# Zio_Qwiic_Micropython_Pyboard_-STM32_V1_.net
KiCad netlist of a schematic drawn in EAGLE
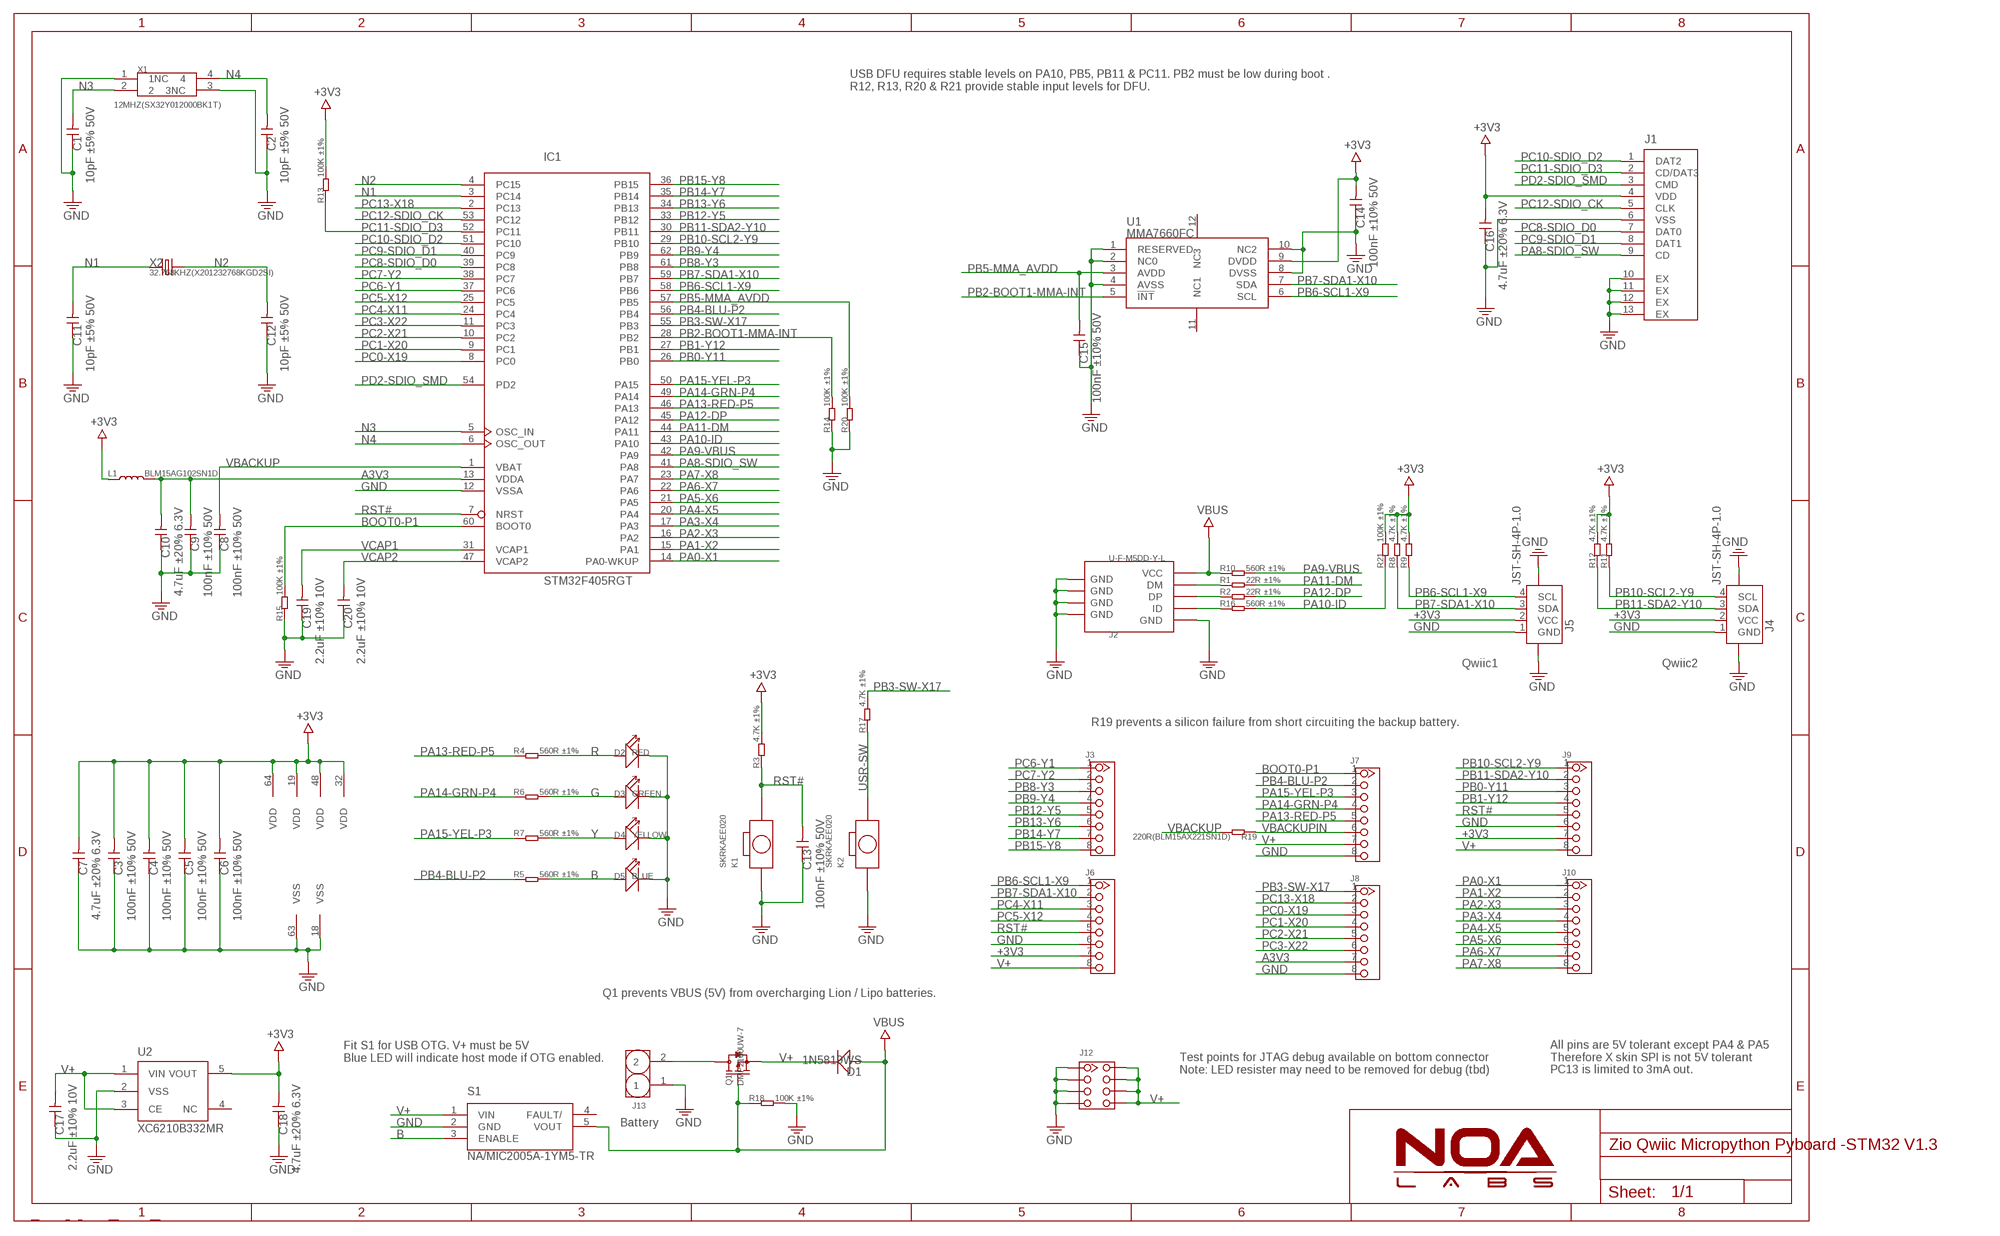
[diagram p0: schematic, sheet 1]

(export (version "E")
  (design (tool "Eeschema 10.0.6"))
  (components
    (comp (ref "C1")
      (value "10pF ±5% 50V")
      (footprint "eagle-import:C0402")
      (libsource (lib "eagle-import") (part "C-0402"))
    )
    (comp (ref "C2")
      (value "10pF ±5% 50V")
      (footprint "eagle-import:C0402")
      (libsource (lib "eagle-import") (part "C-0402"))
    )
    (comp (ref "C3")
      (value "100nF ±10% 50V")
      (footprint "eagle-import:C0402")
      (libsource (lib "eagle-import") (part "C-0402"))
    )
    (comp (ref "C4")
      (value "100nF ±10% 50V")
      (footprint "eagle-import:C0402")
      (libsource (lib "eagle-import") (part "C-0402"))
    )
    (comp (ref "C5")
      (value "100nF ±10% 50V")
      (footprint "eagle-import:C0402")
      (libsource (lib "eagle-import") (part "C-0402"))
    )
    (comp (ref "C6")
      (value "100nF ±10% 50V")
      (footprint "eagle-import:C0402")
      (libsource (lib "eagle-import") (part "C-0402"))
    )
    (comp (ref "C7")
      (value "4.7uF ±20% 6.3V")
      (footprint "eagle-import:C0402")
      (libsource (lib "eagle-import") (part "C-0402"))
    )
    (comp (ref "C8")
      (value "100nF ±10% 50V")
      (footprint "eagle-import:C0402")
      (libsource (lib "eagle-import") (part "C-0402"))
    )
    (comp (ref "C9")
      (value "100nF ±10% 50V")
      (footprint "eagle-import:C0402")
      (libsource (lib "eagle-import") (part "C-0402"))
    )
    (comp (ref "C10")
      (value "4.7uF ±20% 6.3V")
      (footprint "eagle-import:C0402")
      (libsource (lib "eagle-import") (part "C-0402"))
    )
    (comp (ref "C11")
      (value "10pF ±5% 50V")
      (footprint "eagle-import:C0402")
      (libsource (lib "eagle-import") (part "C-0402"))
    )
    (comp (ref "C12")
      (value "10pF ±5% 50V")
      (footprint "eagle-import:C0402")
      (libsource (lib "eagle-import") (part "C-0402"))
    )
    (comp (ref "C13")
      (value "100nF ±10% 50V")
      (footprint "eagle-import:C0402")
      (libsource (lib "eagle-import") (part "C-0402"))
    )
    (comp (ref "C14")
      (value "100nF ±10% 50V")
      (footprint "eagle-import:C0402")
      (libsource (lib "eagle-import") (part "C-0402"))
    )
    (comp (ref "C15")
      (value "100nF ±10% 50V")
      (footprint "eagle-import:C0402")
      (libsource (lib "eagle-import") (part "C-0402"))
    )
    (comp (ref "C16")
      (value "4.7uF ±20% 6.3V")
      (footprint "eagle-import:C0402")
      (libsource (lib "eagle-import") (part "C-0402"))
    )
    (comp (ref "C17")
      (value "2.2uF ±10% 10V")
      (footprint "eagle-import:C0402")
      (libsource (lib "eagle-import") (part "C-0402"))
    )
    (comp (ref "C18")
      (value "4.7uF ±20% 6.3V")
      (footprint "eagle-import:C0402")
      (libsource (lib "eagle-import") (part "C-0402"))
    )
    (comp (ref "C19")
      (value "2.2uF ±10% 10V")
      (footprint "eagle-import:C0402")
      (libsource (lib "eagle-import") (part "C-0402"))
    )
    (comp (ref "C20")
      (value "2.2uF ±10% 10V")
      (footprint "eagle-import:C0402")
      (libsource (lib "eagle-import") (part "C-0402"))
    )
    (comp (ref "D1")
      (value "1N5819WS")
      (footprint "eagle-import:SOD323")
      (libsource (lib "eagle-import") (part "D-0805"))
    )
    (comp (ref "D2")
      (value "RED")
      (footprint "eagle-import:LED-0603")
      (libsource (lib "eagle-import") (part "LED'0603'"))
    )
    (comp (ref "D3")
      (value "GREEN")
      (footprint "eagle-import:LED-0603")
      (libsource (lib "eagle-import") (part "LED'0603'"))
    )
    (comp (ref "D4")
      (value "YELLOW")
      (footprint "eagle-import:LED-0603")
      (libsource (lib "eagle-import") (part "LED'0603'"))
    )
    (comp (ref "D5")
      (value "BLUE")
      (footprint "eagle-import:LED-0603")
      (libsource (lib "eagle-import") (part "LED'0603'"))
    )
    (comp (ref "IC1")
      (value "STM32F405RGT")
      (footprint "eagle-import:LQFP64")
      (libsource (lib "eagle-import") (part "STM32F405RTG"))
    )
    (comp (ref "J1")
      (value "TF_CARD")
      (footprint "eagle-import:TF_CARD")
      (libsource (lib "eagle-import") (part "TF_CARD"))
    )
    (comp (ref "J2")
      (value "U-F-M5DD-Y-L")
      (footprint "eagle-import:MICRO-SMD")
      (libsource (lib "eagle-import") (part "USB-MICROE"))
    )
    (comp (ref "J3")
      (value "HEADER-8P-NS")
      (footprint "eagle-import:8P-2.54-60_35MIL-NS")
      (libsource (lib "eagle-import") (part "HEADER-8P-NS"))
    )
    (comp (ref "J4")
      (value "JST-SH-4P-1.0")
      (footprint "eagle-import:JST-SH-4P")
      (libsource (lib "eagle-import") (part "JST-SH-4P-1.0"))
    )
    (comp (ref "J5")
      (value "JST-SH-4P-1.0")
      (footprint "eagle-import:JST-SH-4P")
      (libsource (lib "eagle-import") (part "JST-SH-4P-1.0"))
    )
    (comp (ref "J6")
      (value "HEADER-8P-NS")
      (footprint "eagle-import:8P-2.54-60_35MIL-NS")
      (libsource (lib "eagle-import") (part "HEADER-8P-NS"))
    )
    (comp (ref "J7")
      (value "HEADER-8P-NS")
      (footprint "eagle-import:8P-2.54-60_35MIL-NS")
      (libsource (lib "eagle-import") (part "HEADER-8P-NS"))
    )
    (comp (ref "J8")
      (value "HEADER-8P-NS")
      (footprint "eagle-import:8P-2.54-60_35MIL-NS")
      (libsource (lib "eagle-import") (part "HEADER-8P-NS"))
    )
    (comp (ref "J9")
      (value "HEADER-8P-NS")
      (footprint "eagle-import:8P-2.54-60_35MIL-NS")
      (libsource (lib "eagle-import") (part "HEADER-8P-NS"))
    )
    (comp (ref "J10")
      (value "HEADER-8P-NS")
      (footprint "eagle-import:8P-2.54-60_35MIL-NS")
      (libsource (lib "eagle-import") (part "HEADER-8P-NS"))
    )
    (comp (ref "J12")
      (value "HEADER-2X4P-NS")
      (footprint "eagle-import:2X4P-2.54-NS")
      (libsource (lib "eagle-import") (part "HEADER-2X4P-NS"))
    )
    (comp (ref "J13")
      (value "HEADER-2P-2.0-90")
      (footprint "eagle-import:PH2.0-2P-90")
      (libsource (lib "eagle-import") (part "HEADER-2P-2.0-90"))
    )
    (comp (ref "K1")
      (value "SKRKAEE020")
      (footprint "eagle-import:SKRKAEE020")
      (libsource (lib "eagle-import") (part "BUTTON-2PSKRKAEE020"))
    )
    (comp (ref "K2")
      (value "SKRKAEE020")
      (footprint "eagle-import:SKRKAEE020")
      (libsource (lib "eagle-import") (part "BUTTON-2PSKRKAEE020"))
    )
    (comp (ref "L1")
      (value "BLM15AG102SN1D")
      (footprint "eagle-import:L0402")
      (libsource (lib "eagle-import") (part "L-0402"))
    )
    (comp (ref "Q1")
      (value "DMP2160UW-7")
      (footprint "eagle-import:SOT-323")
      (libsource (lib "eagle-import") (part "MOSFET-P-323"))
    )
    (comp (ref "R1")
      (value "22R ±1%")
      (footprint "eagle-import:R0402")
      (libsource (lib "eagle-import") (part "R-0402"))
    )
    (comp (ref "R2")
      (value "22R ±1%")
      (footprint "eagle-import:R0402")
      (libsource (lib "eagle-import") (part "R-0402"))
    )
    (comp (ref "R3")
      (value "4.7K ±1%")
      (footprint "eagle-import:R0402")
      (libsource (lib "eagle-import") (part "R-0402"))
    )
    (comp (ref "R4")
      (value "560R ±1%")
      (footprint "eagle-import:R0402")
      (libsource (lib "eagle-import") (part "R-0402"))
    )
    (comp (ref "R5")
      (value "560R ±1%")
      (footprint "eagle-import:R0402")
      (libsource (lib "eagle-import") (part "R-0402"))
    )
    (comp (ref "R6")
      (value "560R ±1%")
      (footprint "eagle-import:R0402")
      (libsource (lib "eagle-import") (part "R-0402"))
    )
    (comp (ref "R7")
      (value "560R ±1%")
      (footprint "eagle-import:R0402")
      (libsource (lib "eagle-import") (part "R-0402"))
    )
    (comp (ref "R8")
      (value "4.7K ±1%")
      (footprint "eagle-import:R0402")
      (libsource (lib "eagle-import") (part "R-0402"))
    )
    (comp (ref "R9")
      (value "4.7K ±1%")
      (footprint "eagle-import:R0402")
      (libsource (lib "eagle-import") (part "R-0402"))
    )
    (comp (ref "R10")
      (value "560R ±1%")
      (footprint "eagle-import:R0402")
      (libsource (lib "eagle-import") (part "R-0402"))
    )
    (comp (ref "R11")
      (value "4.7K ±1%")
      (footprint "eagle-import:R0402")
      (libsource (lib "eagle-import") (part "R-0402"))
    )
    (comp (ref "R12")
      (value "4.7K ±1%")
      (footprint "eagle-import:R0402")
      (libsource (lib "eagle-import") (part "R-0402"))
    )
    (comp (ref "R13")
      (value "100K ±1%")
      (footprint "eagle-import:R0402")
      (libsource (lib "eagle-import") (part "R-0402"))
    )
    (comp (ref "R14")
      (value "100K ±1%")
      (footprint "eagle-import:R0402")
      (libsource (lib "eagle-import") (part "R-0402"))
    )
    (comp (ref "R15")
      (value "100K ±1%")
      (footprint "eagle-import:R0402")
      (libsource (lib "eagle-import") (part "R-0402"))
    )
    (comp (ref "R16")
      (value "560R ±1%")
      (footprint "eagle-import:R0402")
      (libsource (lib "eagle-import") (part "R-0402"))
    )
    (comp (ref "R17")
      (value "4.7K ±1%")
      (footprint "eagle-import:R0402")
      (libsource (lib "eagle-import") (part "R-0402"))
    )
    (comp (ref "R18")
      (value "100K ±1%")
      (footprint "eagle-import:R0402")
      (libsource (lib "eagle-import") (part "R-0402"))
    )
    (comp (ref "R19")
      (value "220R(BLM15AX221SN1D)")
      (footprint "eagle-import:R0402")
      (libsource (lib "eagle-import") (part "R-0402"))
    )
    (comp (ref "R20")
      (value "100K ±1%")
      (footprint "eagle-import:R0402")
      (libsource (lib "eagle-import") (part "R-0402"))
    )
    (comp (ref "R21")
      (value "100K ±1%")
      (footprint "eagle-import:R0402")
      (libsource (lib "eagle-import") (part "R-0402"))
    )
    (comp (ref "S1")
      (value "NA/MIC2005A-1YM5-TR")
      (footprint "eagle-import:SOT95P280X130-5N")
      (fields
        (field (name "ARROW_PART_NUMBER") "MIC2005A-1YM5-TR")
        (field (name "MOUSER_PART_NUMBER") "998-MIC2005A-1YM5TR")
      )
      (libsource (lib "eagle-import") (part "MIC2005A-1YM5-TR"))
    )
    (comp (ref "U1")
      (value "MMA7660FC")
      (footprint "eagle-import:DFN10")
      (libsource (lib "eagle-import") (part "MMA7660FC-DFN10"))
    )
    (comp (ref "U2")
      (value "XC6210B332MR")
      (footprint "eagle-import:SOT23-5")
      (libsource (lib "eagle-import") (part "XC6210"))
    )
    (comp (ref "X1")
      (value "12MHZ(SX32Y012000BK1T)")
      (footprint "eagle-import:4P-SMD-3.2X2.5")
      (libsource (lib "eagle-import") (part "CRYSTAL-XTAL-4P-3225"))
    )
    (comp (ref "X2")
      (value "32.768KHZ(X201232768KGD2SI)")
      (footprint "eagle-import:2.0X12MM")
      (libsource (lib "eagle-import") (part "CRYSTAL-2012"))
    )
  )
  (nets
    (net (code "1") (name "+3V3") (class "Default")
      (node (ref "C14") (pin "2") (pinfunction "2_2") (pintype "passive"))
      (node (ref "C16") (pin "2") (pinfunction "2_2") (pintype "passive"))
      (node (ref "C18") (pin "2") (pinfunction "2_2") (pintype "passive"))
      (node (ref "C3") (pin "2") (pinfunction "2_2") (pintype "passive"))
      (node (ref "C4") (pin "2") (pinfunction "2_2") (pintype "passive"))
      (node (ref "C5") (pin "2") (pinfunction "2_2") (pintype "passive"))
      (node (ref "C6") (pin "2") (pinfunction "2_2") (pintype "passive"))
      (node (ref "C7") (pin "2") (pinfunction "2_2") (pintype "passive"))
      (node (ref "IC1") (pin "19") (pinfunction "VDD_19") (pintype "power_in"))
      (node (ref "IC1") (pin "32") (pinfunction "VDD_32") (pintype "power_in"))
      (node (ref "IC1") (pin "48") (pinfunction "VDD_48") (pintype "power_in"))
      (node (ref "IC1") (pin "64") (pinfunction "VDD_64") (pintype "power_in"))
      (node (ref "J1") (pin "4") (pinfunction "VDD_4") (pintype "bidirectional"))
      (node (ref "J4") (pin "2") (pinfunction "VCC_2") (pintype "bidirectional"))
      (node (ref "J5") (pin "2") (pinfunction "VCC_2") (pintype "bidirectional"))
      (node (ref "J6") (pin "7") (pinfunction "7_7") (pintype "bidirectional"))
      (node (ref "J9") (pin "7") (pinfunction "7_7") (pintype "bidirectional"))
      (node (ref "L1") (pin "1") (pinfunction "1_1") (pintype "passive"))
      (node (ref "R11") (pin "2") (pinfunction "2_2") (pintype "passive"))
      (node (ref "R12") (pin "2") (pinfunction "2_2") (pintype "passive"))
      (node (ref "R13") (pin "2") (pinfunction "2_2") (pintype "passive"))
      (node (ref "R21") (pin "2") (pinfunction "2_2") (pintype "passive"))
      (node (ref "R3") (pin "2") (pinfunction "2_2") (pintype "passive"))
      (node (ref "R8") (pin "2") (pinfunction "2_2") (pintype "passive"))
      (node (ref "R9") (pin "2") (pinfunction "2_2") (pintype "passive"))
      (node (ref "U1") (pin "9") (pinfunction "DVDD_9") (pintype "bidirectional"))
      (node (ref "U2") (pin "5") (pinfunction "VOUT_5") (pintype "bidirectional"))
    )
    (net (code "2") (name "/A3V3") (class "Default")
      (node (ref "C10") (pin "2") (pinfunction "2_2") (pintype "passive"))
      (node (ref "C9") (pin "2") (pinfunction "2_2") (pintype "passive"))
      (node (ref "IC1") (pin "13") (pinfunction "VDDA_13") (pintype "power_in"))
      (node (ref "J8") (pin "7") (pinfunction "7_7") (pintype "bidirectional"))
      (node (ref "L1") (pin "2") (pinfunction "2_2") (pintype "passive"))
    )
    (net (code "3") (name "/B") (class "Default")
      (node (ref "D5") (pin "+") (pinfunction "+_+") (pintype "passive"))
      (node (ref "R5") (pin "2") (pinfunction "2_2") (pintype "passive"))
      (node (ref "S1") (pin "3") (pinfunction "ENABLE_3") (pintype "bidirectional"))
    )
    (net (code "4") (name "/BOOT0-P1") (class "Default")
      (node (ref "IC1") (pin "60") (pinfunction "BOOT0_60") (pintype "input"))
      (node (ref "J7") (pin "1") (pinfunction "1_1") (pintype "bidirectional"))
      (node (ref "R15") (pin "2") (pinfunction "2_2") (pintype "passive"))
    )
    (net (code "5") (name "/G") (class "Default")
      (node (ref "D3") (pin "+") (pinfunction "+_+") (pintype "passive"))
      (node (ref "R6") (pin "2") (pinfunction "2_2") (pintype "passive"))
    )
    (net (code "6") (name "/N1") (class "Default")
      (node (ref "C11") (pin "2") (pinfunction "2_2") (pintype "passive"))
      (node (ref "IC1") (pin "3") (pinfunction "PC14_3") (pintype "bidirectional"))
      (node (ref "X2") (pin "1") (pinfunction "1_1") (pintype "passive"))
    )
    (net (code "7") (name "/N2") (class "Default")
      (node (ref "C12") (pin "2") (pinfunction "2_2") (pintype "passive"))
      (node (ref "IC1") (pin "4") (pinfunction "PC15_4") (pintype "bidirectional"))
      (node (ref "X2") (pin "2") (pinfunction "2_2") (pintype "passive"))
    )
    (net (code "8") (name "/N3") (class "Default")
      (node (ref "C1") (pin "2") (pinfunction "2_2") (pintype "passive"))
      (node (ref "IC1") (pin "5") (pinfunction "OSC_IN_5") (pintype "bidirectional"))
      (node (ref "X1") (pin "2") (pinfunction "2_2") (pintype "bidirectional"))
    )
    (net (code "9") (name "/N4") (class "Default")
      (node (ref "C2") (pin "2") (pinfunction "2_2") (pintype "passive"))
      (node (ref "IC1") (pin "6") (pinfunction "OSC_OUT_6") (pintype "bidirectional"))
      (node (ref "X1") (pin "4") (pinfunction "4_4") (pintype "bidirectional"))
    )
    (net (code "10") (name "/PA0-X1") (class "Default")
      (node (ref "IC1") (pin "14") (pinfunction "PA0-WKUP_14") (pintype "bidirectional"))
      (node (ref "J10") (pin "1") (pinfunction "1_1") (pintype "bidirectional"))
    )
    (net (code "11") (name "/PA1-X2") (class "Default")
      (node (ref "IC1") (pin "15") (pinfunction "PA1_15") (pintype "bidirectional"))
      (node (ref "J10") (pin "2") (pinfunction "2_2") (pintype "bidirectional"))
    )
    (net (code "12") (name "/PA2-X3") (class "Default")
      (node (ref "IC1") (pin "16") (pinfunction "PA2_16") (pintype "bidirectional"))
      (node (ref "J10") (pin "3") (pinfunction "3_3") (pintype "bidirectional"))
    )
    (net (code "13") (name "/PA3-X4") (class "Default")
      (node (ref "IC1") (pin "17") (pinfunction "PA3_17") (pintype "bidirectional"))
      (node (ref "J10") (pin "4") (pinfunction "4_4") (pintype "bidirectional"))
    )
    (net (code "14") (name "/PA4-X5") (class "Default")
      (node (ref "IC1") (pin "20") (pinfunction "PA4_20") (pintype "bidirectional"))
      (node (ref "J10") (pin "5") (pinfunction "5_5") (pintype "bidirectional"))
    )
    (net (code "15") (name "/PA5-X6") (class "Default")
      (node (ref "IC1") (pin "21") (pinfunction "PA5_21") (pintype "bidirectional"))
      (node (ref "J10") (pin "6") (pinfunction "6_6") (pintype "bidirectional"))
    )
    (net (code "16") (name "/PA6-X7") (class "Default")
      (node (ref "IC1") (pin "22") (pinfunction "PA6_22") (pintype "bidirectional"))
      (node (ref "J10") (pin "7") (pinfunction "7_7") (pintype "bidirectional"))
    )
    (net (code "17") (name "/PA7-X8") (class "Default")
      (node (ref "IC1") (pin "23") (pinfunction "PA7_23") (pintype "bidirectional"))
      (node (ref "J10") (pin "8") (pinfunction "8_8") (pintype "bidirectional"))
    )
    (net (code "18") (name "/PA8-SDIO_SW") (class "Default")
      (node (ref "IC1") (pin "41") (pinfunction "PA8_41") (pintype "bidirectional"))
      (node (ref "J1") (pin "9") (pinfunction "CD_9") (pintype "bidirectional"))
    )
    (net (code "19") (name "/PA9-VBUS") (class "Default")
      (node (ref "IC1") (pin "42") (pinfunction "PA9_42") (pintype "bidirectional"))
      (node (ref "R10") (pin "2") (pinfunction "2_2") (pintype "passive"))
    )
    (net (code "20") (name "/PA10-ID") (class "Default")
      (node (ref "IC1") (pin "43") (pinfunction "PA10_43") (pintype "bidirectional"))
      (node (ref "R16") (pin "2") (pinfunction "2_2") (pintype "passive"))
      (node (ref "R21") (pin "1") (pinfunction "1_1") (pintype "passive"))
    )
    (net (code "21") (name "/PA11-DM") (class "Default")
      (node (ref "IC1") (pin "44") (pinfunction "PA11_44") (pintype "bidirectional"))
      (node (ref "R1") (pin "2") (pinfunction "2_2") (pintype "passive"))
    )
    (net (code "22") (name "/PA12-DP") (class "Default")
      (node (ref "IC1") (pin "45") (pinfunction "PA12_45") (pintype "bidirectional"))
      (node (ref "R2") (pin "2") (pinfunction "2_2") (pintype "passive"))
    )
    (net (code "23") (name "/PA13-RED-P5") (class "Default")
      (node (ref "IC1") (pin "46") (pinfunction "PA13_46") (pintype "bidirectional"))
      (node (ref "J7") (pin "5") (pinfunction "5_5") (pintype "bidirectional"))
      (node (ref "R4") (pin "1") (pinfunction "1_1") (pintype "passive"))
    )
    (net (code "24") (name "/PA14-GRN-P4") (class "Default")
      (node (ref "IC1") (pin "49") (pinfunction "PA14_49") (pintype "bidirectional"))
      (node (ref "J7") (pin "4") (pinfunction "4_4") (pintype "bidirectional"))
      (node (ref "R6") (pin "1") (pinfunction "1_1") (pintype "passive"))
    )
    (net (code "25") (name "/PA15-YEL-P3") (class "Default")
      (node (ref "IC1") (pin "50") (pinfunction "PA15_50") (pintype "bidirectional"))
      (node (ref "J7") (pin "3") (pinfunction "3_3") (pintype "bidirectional"))
      (node (ref "R7") (pin "1") (pinfunction "1_1") (pintype "passive"))
    )
    (net (code "26") (name "/PB0-Y11") (class "Default")
      (node (ref "IC1") (pin "26") (pinfunction "PB0_26") (pintype "bidirectional"))
      (node (ref "J9") (pin "3") (pinfunction "3_3") (pintype "bidirectional"))
    )
    (net (code "27") (name "/PB1-Y12") (class "Default")
      (node (ref "IC1") (pin "27") (pinfunction "PB1_27") (pintype "bidirectional"))
      (node (ref "J9") (pin "4") (pinfunction "4_4") (pintype "bidirectional"))
    )
    (net (code "28") (name "/PB2-BOOT1-MMA-INT") (class "Default")
      (node (ref "IC1") (pin "28") (pinfunction "PB2_28") (pintype "bidirectional"))
      (node (ref "R14") (pin "2") (pinfunction "2_2") (pintype "passive"))
      (node (ref "U1") (pin "5") (pinfunction "~{INT}_5") (pintype "bidirectional"))
    )
    (net (code "29") (name "/PB3-SW-X17") (class "Default")
      (node (ref "IC1") (pin "55") (pinfunction "PB3_55") (pintype "bidirectional"))
      (node (ref "J8") (pin "1") (pinfunction "1_1") (pintype "bidirectional"))
      (node (ref "R17") (pin "2") (pinfunction "2_2") (pintype "passive"))
    )
    (net (code "30") (name "/PB4-BLU-P2") (class "Default")
      (node (ref "IC1") (pin "56") (pinfunction "PB4_56") (pintype "bidirectional"))
      (node (ref "J7") (pin "2") (pinfunction "2_2") (pintype "bidirectional"))
      (node (ref "R5") (pin "1") (pinfunction "1_1") (pintype "passive"))
    )
    (net (code "31") (name "/PB5-MMA_AVDD") (class "Default")
      (node (ref "C15") (pin "2") (pinfunction "2_2") (pintype "passive"))
      (node (ref "IC1") (pin "57") (pinfunction "PB5_57") (pintype "bidirectional"))
      (node (ref "R20") (pin "2") (pinfunction "2_2") (pintype "passive"))
      (node (ref "U1") (pin "3") (pinfunction "AVDD_3") (pintype "bidirectional"))
    )
    (net (code "32") (name "/PB6-SCL1-X9") (class "Default")
      (node (ref "IC1") (pin "58") (pinfunction "PB6_58") (pintype "bidirectional"))
      (node (ref "J5") (pin "4") (pinfunction "SCL_4") (pintype "bidirectional"))
      (node (ref "J6") (pin "1") (pinfunction "1_1") (pintype "bidirectional"))
      (node (ref "R9") (pin "1") (pinfunction "1_1") (pintype "passive"))
      (node (ref "U1") (pin "6") (pinfunction "SCL_6") (pintype "bidirectional"))
    )
    (net (code "33") (name "/PB7-SDA1-X10") (class "Default")
      (node (ref "IC1") (pin "59") (pinfunction "PB7_59") (pintype "bidirectional"))
      (node (ref "J5") (pin "3") (pinfunction "SDA_3") (pintype "bidirectional"))
      (node (ref "J6") (pin "2") (pinfunction "2_2") (pintype "bidirectional"))
      (node (ref "R8") (pin "1") (pinfunction "1_1") (pintype "passive"))
      (node (ref "U1") (pin "7") (pinfunction "SDA_7") (pintype "bidirectional"))
    )
    (net (code "34") (name "/PB8-Y3") (class "Default")
      (node (ref "IC1") (pin "61") (pinfunction "PB8_61") (pintype "bidirectional"))
      (node (ref "J3") (pin "3") (pinfunction "3_3") (pintype "bidirectional"))
    )
    (net (code "35") (name "/PB9-Y4") (class "Default")
      (node (ref "IC1") (pin "62") (pinfunction "PB9_62") (pintype "bidirectional"))
      (node (ref "J3") (pin "4") (pinfunction "4_4") (pintype "bidirectional"))
    )
    (net (code "36") (name "/PB10-SCL2-Y9") (class "Default")
      (node (ref "IC1") (pin "29") (pinfunction "PB10_29") (pintype "bidirectional"))
      (node (ref "J4") (pin "4") (pinfunction "SCL_4") (pintype "bidirectional"))
      (node (ref "J9") (pin "1") (pinfunction "1_1") (pintype "bidirectional"))
      (node (ref "R11") (pin "1") (pinfunction "1_1") (pintype "passive"))
    )
    (net (code "37") (name "/PB11-SDA2-Y10") (class "Default")
      (node (ref "IC1") (pin "30") (pinfunction "PB11_30") (pintype "bidirectional"))
      (node (ref "J4") (pin "3") (pinfunction "SDA_3") (pintype "bidirectional"))
      (node (ref "J9") (pin "2") (pinfunction "2_2") (pintype "bidirectional"))
      (node (ref "R12") (pin "1") (pinfunction "1_1") (pintype "passive"))
    )
    (net (code "38") (name "/PB12-Y5") (class "Default")
      (node (ref "IC1") (pin "33") (pinfunction "PB12_33") (pintype "bidirectional"))
      (node (ref "J3") (pin "5") (pinfunction "5_5") (pintype "bidirectional"))
    )
    (net (code "39") (name "/PB13-Y6") (class "Default")
      (node (ref "IC1") (pin "34") (pinfunction "PB13_34") (pintype "bidirectional"))
      (node (ref "J3") (pin "6") (pinfunction "6_6") (pintype "bidirectional"))
    )
    (net (code "40") (name "/PB14-Y7") (class "Default")
      (node (ref "IC1") (pin "35") (pinfunction "PB14_35") (pintype "bidirectional"))
      (node (ref "J3") (pin "7") (pinfunction "7_7") (pintype "bidirectional"))
    )
    (net (code "41") (name "/PB15-Y8") (class "Default")
      (node (ref "IC1") (pin "36") (pinfunction "PB15_36") (pintype "bidirectional"))
      (node (ref "J3") (pin "8") (pinfunction "8_8") (pintype "bidirectional"))
    )
    (net (code "42") (name "/PC0-X19") (class "Default")
      (node (ref "IC1") (pin "8") (pinfunction "PC0_8") (pintype "bidirectional"))
      (node (ref "J8") (pin "3") (pinfunction "3_3") (pintype "bidirectional"))
    )
    (net (code "43") (name "/PC1-X20") (class "Default")
      (node (ref "IC1") (pin "9") (pinfunction "PC1_9") (pintype "bidirectional"))
      (node (ref "J8") (pin "4") (pinfunction "4_4") (pintype "bidirectional"))
    )
    (net (code "44") (name "/PC2-X21") (class "Default")
      (node (ref "IC1") (pin "10") (pinfunction "PC2_10") (pintype "bidirectional"))
      (node (ref "J8") (pin "5") (pinfunction "5_5") (pintype "bidirectional"))
    )
    (net (code "45") (name "/PC3-X22") (class "Default")
      (node (ref "IC1") (pin "11") (pinfunction "PC3_11") (pintype "bidirectional"))
      (node (ref "J8") (pin "6") (pinfunction "6_6") (pintype "bidirectional"))
    )
    (net (code "46") (name "/PC4-X11") (class "Default")
      (node (ref "IC1") (pin "24") (pinfunction "PC4_24") (pintype "bidirectional"))
      (node (ref "J6") (pin "3") (pinfunction "3_3") (pintype "bidirectional"))
    )
    (net (code "47") (name "/PC5-X12") (class "Default")
      (node (ref "IC1") (pin "25") (pinfunction "PC5_25") (pintype "bidirectional"))
      (node (ref "J6") (pin "4") (pinfunction "4_4") (pintype "bidirectional"))
    )
    (net (code "48") (name "/PC6-Y1") (class "Default")
      (node (ref "IC1") (pin "37") (pinfunction "PC6_37") (pintype "bidirectional"))
      (node (ref "J3") (pin "1") (pinfunction "1_1") (pintype "bidirectional"))
    )
    (net (code "49") (name "/PC7-Y2") (class "Default")
      (node (ref "IC1") (pin "38") (pinfunction "PC7_38") (pintype "bidirectional"))
      (node (ref "J3") (pin "2") (pinfunction "2_2") (pintype "bidirectional"))
    )
    (net (code "50") (name "/PC8-SDIO_D0") (class "Default")
      (node (ref "IC1") (pin "39") (pinfunction "PC8_39") (pintype "bidirectional"))
      (node (ref "J1") (pin "7") (pinfunction "DAT0_7") (pintype "bidirectional"))
    )
    (net (code "51") (name "/PC9-SDIO_D1") (class "Default")
      (node (ref "IC1") (pin "40") (pinfunction "PC9_40") (pintype "bidirectional"))
      (node (ref "J1") (pin "8") (pinfunction "DAT1_8") (pintype "bidirectional"))
    )
    (net (code "52") (name "/PC10-SDIO_D2") (class "Default")
      (node (ref "IC1") (pin "51") (pinfunction "PC10_51") (pintype "bidirectional"))
      (node (ref "J1") (pin "1") (pinfunction "DAT2_1") (pintype "bidirectional"))
    )
    (net (code "53") (name "/PC11-SDIO_D3") (class "Default")
      (node (ref "IC1") (pin "52") (pinfunction "PC11_52") (pintype "bidirectional"))
      (node (ref "J1") (pin "2") (pinfunction "CD/DAT3_2") (pintype "bidirectional"))
      (node (ref "R13") (pin "1") (pinfunction "1_1") (pintype "passive"))
    )
    (net (code "54") (name "/PC12-SDIO_CK") (class "Default")
      (node (ref "IC1") (pin "53") (pinfunction "PC12_53") (pintype "bidirectional"))
      (node (ref "J1") (pin "5") (pinfunction "CLK_5") (pintype "bidirectional"))
    )
    (net (code "55") (name "/PC13-X18") (class "Default")
      (node (ref "IC1") (pin "2") (pinfunction "PC13_2") (pintype "bidirectional"))
      (node (ref "J8") (pin "2") (pinfunction "2_2") (pintype "bidirectional"))
    )
    (net (code "56") (name "/PD2-SDIO_SMD") (class "Default")
      (node (ref "IC1") (pin "54") (pinfunction "PD2_54") (pintype "bidirectional"))
      (node (ref "J1") (pin "3") (pinfunction "CMD_3") (pintype "bidirectional"))
    )
    (net (code "57") (name "/R") (class "Default")
      (node (ref "D2") (pin "+") (pinfunction "+_+") (pintype "passive"))
      (node (ref "R4") (pin "2") (pinfunction "2_2") (pintype "passive"))
    )
    (net (code "58") (name "/RST#") (class "Default")
      (node (ref "C13") (pin "2") (pinfunction "2_2") (pintype "passive"))
      (node (ref "IC1") (pin "7") (pinfunction "NRST_7") (pintype "bidirectional"))
      (node (ref "J6") (pin "5") (pinfunction "5_5") (pintype "bidirectional"))
      (node (ref "J9") (pin "5") (pinfunction "5_5") (pintype "bidirectional"))
      (node (ref "K1") (pin "2") (pinfunction "2_2") (pintype "bidirectional"))
      (node (ref "R3") (pin "1") (pinfunction "1_1") (pintype "passive"))
    )
    (net (code "59") (name "/USR-SW") (class "Default")
      (node (ref "K2") (pin "2") (pinfunction "2_2") (pintype "bidirectional"))
      (node (ref "R17") (pin "1") (pinfunction "1_1") (pintype "passive"))
    )
    (net (code "60") (name "/V+") (class "Default")
      (node (ref "C17") (pin "2") (pinfunction "2_2") (pintype "passive"))
      (node (ref "D1") (pin "-") (pinfunction "-_-") (pintype "passive"))
      (node (ref "J12") (pin "5") (pinfunction "5_5") (pintype "bidirectional"))
      (node (ref "J12") (pin "6") (pinfunction "6_6") (pintype "bidirectional"))
      (node (ref "J12") (pin "7") (pinfunction "7_7") (pintype "bidirectional"))
      (node (ref "J12") (pin "8") (pinfunction "8_8") (pintype "bidirectional"))
      (node (ref "J6") (pin "8") (pinfunction "8_8") (pintype "bidirectional"))
      (node (ref "J7") (pin "7") (pinfunction "7_7") (pintype "bidirectional"))
      (node (ref "J9") (pin "8") (pinfunction "8_8") (pintype "bidirectional"))
      (node (ref "Q1") (pin "2") (pinfunction "S_2") (pintype "passive"))
      (node (ref "S1") (pin "1") (pinfunction "VIN_1") (pintype "bidirectional"))
      (node (ref "U2") (pin "1") (pinfunction "VIN_1") (pintype "bidirectional"))
      (node (ref "U2") (pin "3") (pinfunction "CE_3") (pintype "bidirectional"))
    )
    (net (code "61") (name "/VBACKUP") (class "Default")
      (node (ref "C8") (pin "2") (pinfunction "2_2") (pintype "passive"))
      (node (ref "IC1") (pin "1") (pinfunction "VBAT_1") (pintype "power_in"))
      (node (ref "R19") (pin "2") (pinfunction "2_2") (pintype "passive"))
    )
    (net (code "62") (name "/VBACKUPIN") (class "Default")
      (node (ref "J7") (pin "6") (pinfunction "6_6") (pintype "bidirectional"))
      (node (ref "R19") (pin "1") (pinfunction "1_1") (pintype "passive"))
    )
    (net (code "63") (name "/VCAP1") (class "Default")
      (node (ref "C19") (pin "2") (pinfunction "2_2") (pintype "passive"))
      (node (ref "IC1") (pin "31") (pinfunction "VCAP1_31") (pintype "power_in"))
    )
    (net (code "64") (name "/VCAP2") (class "Default")
      (node (ref "C20") (pin "2") (pinfunction "2_2") (pintype "passive"))
      (node (ref "IC1") (pin "47") (pinfunction "VCAP2_47") (pintype "power_in"))
    )
    (net (code "65") (name "/Y") (class "Default")
      (node (ref "D4") (pin "+") (pinfunction "+_+") (pintype "passive"))
      (node (ref "R7") (pin "2") (pinfunction "2_2") (pintype "passive"))
    )
    (net (code "66") (name "GND") (class "Default")
      (node (ref "C1") (pin "1") (pinfunction "1_1") (pintype "passive"))
      (node (ref "C10") (pin "1") (pinfunction "1_1") (pintype "passive"))
      (node (ref "C11") (pin "1") (pinfunction "1_1") (pintype "passive"))
      (node (ref "C12") (pin "1") (pinfunction "1_1") (pintype "passive"))
      (node (ref "C13") (pin "1") (pinfunction "1_1") (pintype "passive"))
      (node (ref "C14") (pin "1") (pinfunction "1_1") (pintype "passive"))
      (node (ref "C15") (pin "1") (pinfunction "1_1") (pintype "passive"))
      (node (ref "C16") (pin "1") (pinfunction "1_1") (pintype "passive"))
      (node (ref "C17") (pin "1") (pinfunction "1_1") (pintype "passive"))
      (node (ref "C18") (pin "1") (pinfunction "1_1") (pintype "passive"))
      (node (ref "C19") (pin "1") (pinfunction "1_1") (pintype "passive"))
      (node (ref "C2") (pin "1") (pinfunction "1_1") (pintype "passive"))
      (node (ref "C20") (pin "1") (pinfunction "1_1") (pintype "passive"))
      (node (ref "C3") (pin "1") (pinfunction "1_1") (pintype "passive"))
      (node (ref "C4") (pin "1") (pinfunction "1_1") (pintype "passive"))
      (node (ref "C5") (pin "1") (pinfunction "1_1") (pintype "passive"))
      (node (ref "C6") (pin "1") (pinfunction "1_1") (pintype "passive"))
      (node (ref "C7") (pin "1") (pinfunction "1_1") (pintype "passive"))
      (node (ref "C8") (pin "1") (pinfunction "1_1") (pintype "passive"))
      (node (ref "C9") (pin "1") (pinfunction "1_1") (pintype "passive"))
      (node (ref "D2") (pin "-") (pinfunction "-_-") (pintype "passive"))
      (node (ref "D3") (pin "-") (pinfunction "-_-") (pintype "passive"))
      (node (ref "D4") (pin "-") (pinfunction "-_-") (pintype "passive"))
      (node (ref "D5") (pin "-") (pinfunction "-_-") (pintype "passive"))
      (node (ref "IC1") (pin "12") (pinfunction "VSSA_12") (pintype "power_in"))
      (node (ref "IC1") (pin "18") (pinfunction "VSS_18") (pintype "power_in"))
      (node (ref "IC1") (pin "63") (pinfunction "VSS_63") (pintype "power_in"))
      (node (ref "J1") (pin "10") (pinfunction "EX_10") (pintype "bidirectional"))
      (node (ref "J1") (pin "11") (pinfunction "EX_11") (pintype "bidirectional"))
      (node (ref "J1") (pin "12") (pinfunction "EX_12") (pintype "bidirectional"))
      (node (ref "J1") (pin "13") (pinfunction "EX_13") (pintype "bidirectional"))
      (node (ref "J1") (pin "6") (pinfunction "VSS_6") (pintype "bidirectional"))
      (node (ref "J12") (pin "1") (pinfunction "1_1") (pintype "bidirectional"))
      (node (ref "J12") (pin "2") (pinfunction "2_2") (pintype "bidirectional"))
      (node (ref "J12") (pin "3") (pinfunction "3_3") (pintype "bidirectional"))
      (node (ref "J12") (pin "4") (pinfunction "4_4") (pintype "bidirectional"))
      (node (ref "J13") (pin "1") (pinfunction "1_1") (pintype "bidirectional"))
      (node (ref "J2") (pin "GND") (pinfunction "GND_GND") (pintype "bidirectional"))
      (node (ref "J2") (pin "S1") (pinfunction "GND_S1") (pintype "bidirectional"))
      (node (ref "J2") (pin "S1@1") (pinfunction "GND_S1@1") (pintype "bidirectional"))
      (node (ref "J2") (pin "S1@2") (pinfunction "GND_S1@2") (pintype "bidirectional"))
      (node (ref "J2") (pin "S2") (pinfunction "GND_S2") (pintype "bidirectional"))
      (node (ref "J2") (pin "S2@1") (pinfunction "GND_S2@1") (pintype "bidirectional"))
      (node (ref "J2") (pin "S2@2") (pinfunction "GND_S2@2") (pintype "bidirectional"))
      (node (ref "J2") (pin "S3") (pinfunction "GND_S3") (pintype "bidirectional"))
      (node (ref "J2") (pin "S3@1") (pinfunction "GND_S3@1") (pintype "bidirectional"))
      (node (ref "J2") (pin "S3@2") (pinfunction "GND_S3@2") (pintype "bidirectional"))
      (node (ref "J2") (pin "S4") (pinfunction "GND_S4") (pintype "bidirectional"))
      (node (ref "J2") (pin "S4@1") (pinfunction "GND_S4@1") (pintype "bidirectional"))
      (node (ref "J2") (pin "S4@2") (pinfunction "GND_S4@2") (pintype "bidirectional"))
      (node (ref "J2") (pin "S5") (pinfunction "GND_S5") (pintype "bidirectional"))
      (node (ref "J2") (pin "S6") (pinfunction "GND_S6") (pintype "bidirectional"))
      (node (ref "J4") (pin "1") (pinfunction "GND_1") (pintype "bidirectional"))
      (node (ref "J4") (pin "NC1") (pinfunction "5_NC1") (pintype "bidirectional"))
      (node (ref "J4") (pin "NC2") (pinfunction "6_NC2") (pintype "bidirectional"))
      (node (ref "J5") (pin "1") (pinfunction "GND_1") (pintype "bidirectional"))
      (node (ref "J5") (pin "NC1") (pinfunction "5_NC1") (pintype "bidirectional"))
      (node (ref "J5") (pin "NC2") (pinfunction "6_NC2") (pintype "bidirectional"))
      (node (ref "J6") (pin "6") (pinfunction "6_6") (pintype "bidirectional"))
      (node (ref "J7") (pin "8") (pinfunction "8_8") (pintype "bidirectional"))
      (node (ref "J8") (pin "8") (pinfunction "8_8") (pintype "bidirectional"))
      (node (ref "J9") (pin "6") (pinfunction "6_6") (pintype "bidirectional"))
      (node (ref "K1") (pin "1") (pinfunction "1_1") (pintype "bidirectional"))
      (node (ref "K2") (pin "1") (pinfunction "1_1") (pintype "bidirectional"))
      (node (ref "R14") (pin "1") (pinfunction "1_1") (pintype "passive"))
      (node (ref "R15") (pin "1") (pinfunction "1_1") (pintype "passive"))
      (node (ref "R18") (pin "2") (pinfunction "2_2") (pintype "passive"))
      (node (ref "R20") (pin "1") (pinfunction "1_1") (pintype "passive"))
      (node (ref "S1") (pin "2") (pinfunction "GND_2") (pintype "bidirectional"))
      (node (ref "U1") (pin "1") (pinfunction "RESERVED_1") (pintype "bidirectional"))
      (node (ref "U1") (pin "10") (pinfunction "NC2_10") (pintype "bidirectional"))
      (node (ref "U1") (pin "2") (pinfunction "NC0_2") (pintype "bidirectional"))
      (node (ref "U1") (pin "4") (pinfunction "AVSS_4") (pintype "bidirectional"))
      (node (ref "U1") (pin "8") (pinfunction "DVSS_8") (pintype "bidirectional"))
      (node (ref "U2") (pin "2") (pinfunction "VSS_2") (pintype "bidirectional"))
      (node (ref "X1") (pin "1") (pinfunction "1NC_1") (pintype "bidirectional"))
      (node (ref "X1") (pin "3") (pinfunction "3NC_3") (pintype "bidirectional"))
    )
    (net (code "67") (name "Net-(J2-DM)") (class "Default")
      (node (ref "J2") (pin "D-") (pinfunction "DM_D-") (pintype "bidirectional"))
      (node (ref "R1") (pin "1") (pinfunction "1_1") (pintype "passive"))
    )
    (net (code "68") (name "Net-(J2-DP)") (class "Default")
      (node (ref "J2") (pin "D+") (pinfunction "DP_D+") (pintype "bidirectional"))
      (node (ref "R2") (pin "1") (pinfunction "1_1") (pintype "passive"))
    )
    (net (code "69") (name "Net-(J2-PadID)") (class "Default")
      (node (ref "J2") (pin "ID") (pinfunction "ID_ID") (pintype "bidirectional"))
      (node (ref "R16") (pin "1") (pinfunction "1_1") (pintype "passive"))
    )
    (net (code "70") (name "Net-(Q1-D)") (class "Default")
      (node (ref "J13") (pin "2") (pinfunction "2_2") (pintype "bidirectional"))
      (node (ref "Q1") (pin "3") (pinfunction "D_3") (pintype "passive"))
    )
    (net (code "71") (name "VBUS") (class "Default")
      (node (ref "D1") (pin "+") (pinfunction "+_+") (pintype "passive"))
      (node (ref "J2") (pin "VBUS") (pinfunction "VCC_VBUS") (pintype "bidirectional"))
      (node (ref "Q1") (pin "1") (pinfunction "G_1") (pintype "passive"))
      (node (ref "R10") (pin "1") (pinfunction "1_1") (pintype "passive"))
      (node (ref "R18") (pin "1") (pinfunction "1_1") (pintype "passive"))
      (node (ref "S1") (pin "5") (pinfunction "VOUT_5") (pintype "bidirectional"))
    )
    (net (code "72") (name "unconnected-(S1-FAULT{slash}-Pad4)") (class "Default")
      (node (ref "S1") (pin "4") (pinfunction "FAULT/_4") (pintype "bidirectional"))
    )
    (net (code "73") (name "unconnected-(U1-NC1-Pad11)") (class "Default")
      (node (ref "U1") (pin "11") (pinfunction "NC1_11") (pintype "bidirectional"))
    )
    (net (code "74") (name "unconnected-(U1-NC3-Pad12)") (class "Default")
      (node (ref "U1") (pin "12") (pinfunction "NC3_12") (pintype "bidirectional"))
    )
    (net (code "75") (name "unconnected-(U2-NC-Pad4)") (class "Default")
      (node (ref "U2") (pin "4") (pinfunction "NC_4") (pintype "bidirectional"))
    )
  )
)
